# Inverted_Pendulum_Cape.net
KiCad netlist of a schematic drawn in Altium Designer
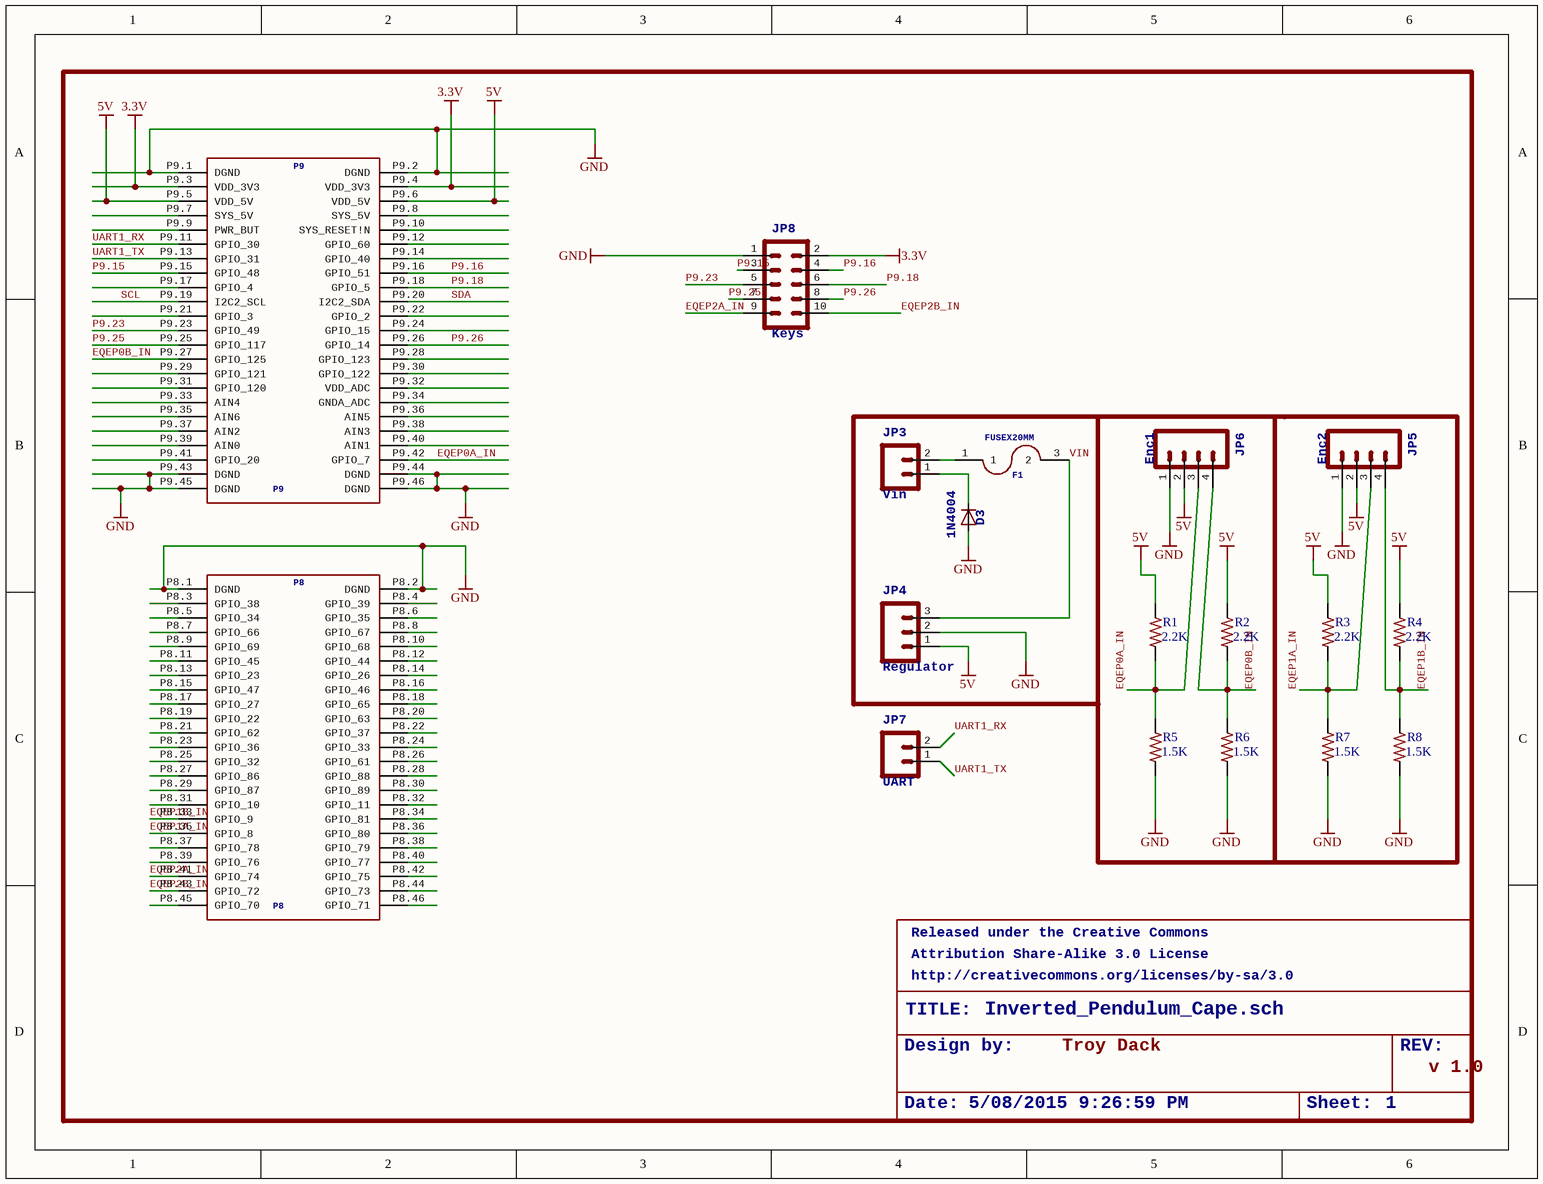
[diagram p0: Inverted_Pendulum_Cape.SchDoc]

(export (version "E")
  (design (tool "Eeschema 10.0.6"))
  (components
    (comp (ref "D3")
      (value "1N4004")
      (footprint "DO41-10")
      (description "<B>DIODE</B><p>\ngeneral purpose rectifier, 1 A")
      (libsource (lib "diode") (part "1N4004"))
    )
    (comp (ref "F1")
      (value "FUSEX20MM")
      (footprint "FUSE_5MM")
      (libsource (lib "SparkFun-Passives") (part "FUSEX20MM"))
    )
    (comp (ref "JP3")
      (value "Vin")
      (footprint "MOLEX-1X2")
      (fields
        (field (name "MF") "MOLEX")
        (field (name "MPN") "22-27-2021")
        (field (name ">VALUE") "Vin")
        (field (name ">NAME") "JP3")
      )
      (libsource (lib "SparkFun-Connectors") (part "M02POLAR"))
    )
    (comp (ref "JP4")
      (value "Regulator")
      (footprint "1X03")
      (fields
        (field (name "MF") "MURATA POWER SOLUTIONS")
        (field (name "MPN") "OKI-78SR-5/1.5-W36-C.")
        (field (name ">VALUE") "Regulator")
        (field (name ">NAME") "JP4")
      )
      (libsource (lib "SparkFun-Connectors") (part "M03PTH"))
    )
    (comp (ref "JP5")
      (value "Enc2")
      (footprint "MOLEX-1X4")
      (fields
        (field (name "MF") "MOLEX")
        (field (name "MPN") "22-27-2041")
        (field (name ">VALUE") "Enc2")
        (field (name ">NAME") "JP5")
      )
      (libsource (lib "SparkFun-Connectors") (part "M04POLAR"))
    )
    (comp (ref "JP6")
      (value "Enc1")
      (footprint "MOLEX-1X4")
      (fields
        (field (name "MF") "MOLEX")
        (field (name "MPN") "22-27-2041")
        (field (name ">VALUE") "Enc1")
        (field (name ">NAME") "JP6")
      )
      (libsource (lib "SparkFun-Connectors") (part "M04POLAR"))
    )
    (comp (ref "JP7")
      (value "UART")
      (footprint "MOLEX-1X2")
      (fields
        (field (name "MF") "MOLEX")
        (field (name "MPN") "22-27-2021")
        (field (name ">VALUE") "UART")
        (field (name ">NAME") "JP7")
      )
      (libsource (lib "SparkFun-Connectors") (part "M02POLAR"))
    )
    (comp (ref "JP8")
      (value "Keys")
      (footprint "2X5_PTH_SILK_.05")
      (libsource (lib "SparkFun-Connectors") (part "M05X20.05_IN_PTH_SILK"))
    )
    (comp (ref "R1")
      (value "2.2K")
      (footprint "1206")
      (fields (field (name "Comment") "RESISTOR1206"))
      (libsource (lib "SparkFun-Passives") (part "RESISTOR1206"))
    )
    (comp (ref "R2")
      (value "2.2K")
      (footprint "1206")
      (fields (field (name "Comment") "RESISTOR1206"))
      (libsource (lib "SparkFun-Passives") (part "RESISTOR1206"))
    )
    (comp (ref "R3")
      (value "2.2K")
      (footprint "1206")
      (fields (field (name "Comment") "RESISTOR1206"))
      (libsource (lib "SparkFun-Passives") (part "RESISTOR1206"))
    )
    (comp (ref "R4")
      (value "2.2K")
      (footprint "1206")
      (fields (field (name "Comment") "RESISTOR1206"))
      (libsource (lib "SparkFun-Passives") (part "RESISTOR1206"))
    )
    (comp (ref "R5")
      (value "1.5K")
      (footprint "1206")
      (fields (field (name "Comment") "RESISTOR1206"))
      (libsource (lib "SparkFun-Passives") (part "RESISTOR1206"))
    )
    (comp (ref "R6")
      (value "1.5K")
      (footprint "1206")
      (fields (field (name "Comment") "RESISTOR1206"))
      (libsource (lib "SparkFun-Passives") (part "RESISTOR1206"))
    )
    (comp (ref "R7")
      (value "1.5K")
      (footprint "1206")
      (fields (field (name "Comment") "RESISTOR1206"))
      (libsource (lib "SparkFun-Passives") (part "RESISTOR1206"))
    )
    (comp (ref "R8")
      (value "1.5K")
      (footprint "1206")
      (fields (field (name "Comment") "RESISTOR1206"))
      (libsource (lib "SparkFun-Passives") (part "RESISTOR1206"))
    )
    (comp (ref "U$1")
      (value "BEAGLE_BONE_BLACK_CAPE")
      (footprint "BEAGLE_BONE_BLACK_CAPE")
      (fields
        (field (name "P8") "P8")
        (field (name "P8_1") "P8")
        (field (name "P9") "P9")
        (field (name "P9_1") "P9")
      )
      (libsource (lib "SparkFun-Boards") (part "BEAGLE_BONE_BLACK_CAPE"))
    )
  )
  (nets
    (net (code "1") (name "/EQEP0A_IN") (class "Default")
      (node (ref "JP6") (pin "3") (pinfunction "3_3") (pintype "passive"))
      (node (ref "R1") (pin "2") (pinfunction "2_2") (pintype "passive"))
      (node (ref "R5") (pin "1") (pinfunction "1_1") (pintype "passive"))
      (node (ref "U$1") (pin "P9.42") (pinfunction "GPIO_7_P9.42") (pintype "passive"))
    )
    (net (code "2") (name "/EQEP0B_IN") (class "Default")
      (node (ref "JP6") (pin "4") (pinfunction "4_4") (pintype "passive"))
      (node (ref "R2") (pin "2") (pinfunction "2_2") (pintype "passive"))
      (node (ref "R6") (pin "1") (pinfunction "1_1") (pintype "passive"))
      (node (ref "U$1") (pin "P9.27") (pinfunction "GPIO_125_P9.27") (pintype "passive"))
    )
    (net (code "3") (name "/EQEP1A_IN") (class "Default")
      (node (ref "JP5") (pin "3") (pinfunction "3_3") (pintype "passive"))
      (node (ref "R3") (pin "2") (pinfunction "2_2") (pintype "passive"))
      (node (ref "R7") (pin "1") (pinfunction "1_1") (pintype "passive"))
      (node (ref "U$1") (pin "P8.35") (pinfunction "GPIO_8_P8.35") (pintype "passive"))
    )
    (net (code "4") (name "/EQEP1B_IN") (class "Default")
      (node (ref "JP5") (pin "4") (pinfunction "4_4") (pintype "passive"))
      (node (ref "R4") (pin "2") (pinfunction "2_2") (pintype "passive"))
      (node (ref "R8") (pin "1") (pinfunction "1_1") (pintype "passive"))
      (node (ref "U$1") (pin "P8.33") (pinfunction "GPIO_9_P8.33") (pintype "passive"))
    )
    (net (code "5") (name "/EQEP2A_IN") (class "Default")
      (node (ref "JP8") (pin "9") (pinfunction "9_9") (pintype "passive"))
      (node (ref "U$1") (pin "P8.41") (pinfunction "GPIO_74_P8.41") (pintype "passive"))
    )
    (net (code "6") (name "/EQEP2B_IN") (class "Default")
      (node (ref "JP8") (pin "10") (pinfunction "10_10") (pintype "passive"))
      (node (ref "U$1") (pin "P8.43") (pinfunction "GPIO_72_P8.43") (pintype "passive"))
    )
    (net (code "7") (name "/P9.15") (class "Default")
      (node (ref "JP8") (pin "3") (pinfunction "3_3") (pintype "passive"))
      (node (ref "U$1") (pin "P9.15") (pinfunction "GPIO_48_P9.15") (pintype "passive"))
    )
    (net (code "8") (name "/P9.16") (class "Default")
      (node (ref "JP8") (pin "4") (pinfunction "4_4") (pintype "passive"))
      (node (ref "U$1") (pin "P9.16") (pinfunction "GPIO_51_P9.16") (pintype "passive"))
    )
    (net (code "9") (name "/P9.18") (class "Default")
      (node (ref "JP8") (pin "6") (pinfunction "6_6") (pintype "passive"))
      (node (ref "U$1") (pin "P9.18") (pinfunction "GPIO_5_P9.18") (pintype "passive"))
    )
    (net (code "10") (name "/P9.23") (class "Default")
      (node (ref "JP8") (pin "5") (pinfunction "5_5") (pintype "passive"))
      (node (ref "U$1") (pin "P9.23") (pinfunction "GPIO_49_P9.23") (pintype "passive"))
    )
    (net (code "11") (name "/P9.25") (class "Default")
      (node (ref "JP8") (pin "7") (pinfunction "7_7") (pintype "passive"))
      (node (ref "U$1") (pin "P9.25") (pinfunction "GPIO_117_P9.25") (pintype "passive"))
    )
    (net (code "12") (name "/P9.26") (class "Default")
      (node (ref "JP8") (pin "8") (pinfunction "8_8") (pintype "passive"))
      (node (ref "U$1") (pin "P9.26") (pinfunction "GPIO_14_P9.26") (pintype "passive"))
    )
    (net (code "13") (name "/SCL") (class "Default")
      (node (ref "U$1") (pin "P9.19") (pinfunction "I2C2_SCL_P9.19") (pintype "passive"))
    )
    (net (code "14") (name "/SDA") (class "Default")
      (node (ref "U$1") (pin "P9.20") (pinfunction "I2C2_SDA_P9.20") (pintype "passive"))
    )
    (net (code "15") (name "/UART1_RX") (class "Default")
      (node (ref "JP7") (pin "2") (pinfunction "2_2") (pintype "passive"))
      (node (ref "U$1") (pin "P9.11") (pinfunction "GPIO_30_P9.11") (pintype "passive"))
    )
    (net (code "16") (name "/UART1_TX") (class "Default")
      (node (ref "JP7") (pin "1") (pinfunction "1_1") (pintype "passive"))
      (node (ref "U$1") (pin "P9.13") (pinfunction "GPIO_31_P9.13") (pintype "passive"))
    )
    (net (code "17") (name "/VIN") (class "Default")
      (node (ref "F1") (pin "3") (pinfunction "2_3") (pintype "passive"))
      (node (ref "JP4") (pin "3") (pinfunction "3_3") (pintype "passive"))
    )
    (net (code "18") (name "3.3V") (class "Default")
      (node (ref "JP8") (pin "2") (pinfunction "2_2") (pintype "passive"))
      (node (ref "U$1") (pin "P9.3") (pinfunction "VDD_3V3_P9.3") (pintype "passive"))
      (node (ref "U$1") (pin "P9.4") (pinfunction "VDD_3V3_P9.4") (pintype "passive"))
    )
    (net (code "19") (name "5V") (class "Default")
      (node (ref "JP4") (pin "1") (pinfunction "1_1") (pintype "passive"))
      (node (ref "JP5") (pin "2") (pinfunction "2_2") (pintype "passive"))
      (node (ref "JP6") (pin "2") (pinfunction "2_2") (pintype "passive"))
      (node (ref "R1") (pin "1") (pinfunction "1_1") (pintype "passive"))
      (node (ref "R2") (pin "1") (pinfunction "1_1") (pintype "passive"))
      (node (ref "R3") (pin "1") (pinfunction "1_1") (pintype "passive"))
      (node (ref "R4") (pin "1") (pinfunction "1_1") (pintype "passive"))
      (node (ref "U$1") (pin "P9.5") (pinfunction "VDD_5V_P9.5") (pintype "passive"))
      (node (ref "U$1") (pin "P9.6") (pinfunction "VDD_5V_P9.6") (pintype "passive"))
    )
    (net (code "20") (name "GND") (class "Default")
      (node (ref "D3") (pin "A") (pinfunction "A_A") (pintype "passive"))
      (node (ref "JP4") (pin "2") (pinfunction "2_2") (pintype "passive"))
      (node (ref "JP5") (pin "1") (pinfunction "1_1") (pintype "passive"))
      (node (ref "JP6") (pin "1") (pinfunction "1_1") (pintype "passive"))
      (node (ref "JP8") (pin "1") (pinfunction "1_1") (pintype "passive"))
      (node (ref "R5") (pin "2") (pinfunction "2_2") (pintype "passive"))
      (node (ref "R6") (pin "2") (pinfunction "2_2") (pintype "passive"))
      (node (ref "R7") (pin "2") (pinfunction "2_2") (pintype "passive"))
      (node (ref "R8") (pin "2") (pinfunction "2_2") (pintype "passive"))
      (node (ref "U$1") (pin "P8.1") (pinfunction "DGND_P8.1") (pintype "passive"))
      (node (ref "U$1") (pin "P8.2") (pinfunction "DGND_P8.2") (pintype "passive"))
      (node (ref "U$1") (pin "P9.1") (pinfunction "DGND_P9.1") (pintype "passive"))
      (node (ref "U$1") (pin "P9.2") (pinfunction "DGND_P9.2") (pintype "passive"))
      (node (ref "U$1") (pin "P9.43") (pinfunction "DGND_P9.43") (pintype "passive"))
      (node (ref "U$1") (pin "P9.44") (pinfunction "DGND_P9.44") (pintype "passive"))
      (node (ref "U$1") (pin "P9.45") (pinfunction "DGND_P9.45") (pintype "passive"))
      (node (ref "U$1") (pin "P9.46") (pinfunction "DGND_P9.46") (pintype "passive"))
    )
    (net (code "21") (name "Net-(D3-PadC)") (class "Default")
      (node (ref "D3") (pin "C") (pinfunction "C_C") (pintype "passive"))
      (node (ref "JP3") (pin "1") (pinfunction "1_1") (pintype "passive"))
    )
    (net (code "22") (name "Net-(F1-Pad1)") (class "Default")
      (node (ref "F1") (pin "1") (pinfunction "1_1") (pintype "passive"))
      (node (ref "JP3") (pin "2") (pinfunction "2_2") (pintype "passive"))
    )
    (net (code "23") (name "unconnected-(U$1A-GPIO_10-PadP8.31)") (class "Default")
      (node (ref "U$1") (pin "P8.31") (pinfunction "GPIO_10_P8.31") (pintype "passive"))
    )
    (net (code "24") (name "unconnected-(U$1A-GPIO_11-PadP8.32)") (class "Default")
      (node (ref "U$1") (pin "P8.32") (pinfunction "GPIO_11_P8.32") (pintype "passive"))
    )
    (net (code "25") (name "unconnected-(U$1A-GPIO_22-PadP8.19)") (class "Default")
      (node (ref "U$1") (pin "P8.19") (pinfunction "GPIO_22_P8.19") (pintype "passive"))
    )
    (net (code "26") (name "unconnected-(U$1A-GPIO_23-PadP8.13)") (class "Default")
      (node (ref "U$1") (pin "P8.13") (pinfunction "GPIO_23_P8.13") (pintype "passive"))
    )
    (net (code "27") (name "unconnected-(U$1A-GPIO_26-PadP8.14)") (class "Default")
      (node (ref "U$1") (pin "P8.14") (pinfunction "GPIO_26_P8.14") (pintype "passive"))
    )
    (net (code "28") (name "unconnected-(U$1A-GPIO_27-PadP8.17)") (class "Default")
      (node (ref "U$1") (pin "P8.17") (pinfunction "GPIO_27_P8.17") (pintype "passive"))
    )
    (net (code "29") (name "unconnected-(U$1A-GPIO_32-PadP8.25)") (class "Default")
      (node (ref "U$1") (pin "P8.25") (pinfunction "GPIO_32_P8.25") (pintype "passive"))
    )
    (net (code "30") (name "unconnected-(U$1A-GPIO_33-PadP8.24)") (class "Default")
      (node (ref "U$1") (pin "P8.24") (pinfunction "GPIO_33_P8.24") (pintype "passive"))
    )
    (net (code "31") (name "unconnected-(U$1A-GPIO_34-PadP8.5)") (class "Default")
      (node (ref "U$1") (pin "P8.5") (pinfunction "GPIO_34_P8.5") (pintype "passive"))
    )
    (net (code "32") (name "unconnected-(U$1A-GPIO_35-PadP8.6)") (class "Default")
      (node (ref "U$1") (pin "P8.6") (pinfunction "GPIO_35_P8.6") (pintype "passive"))
    )
    (net (code "33") (name "unconnected-(U$1A-GPIO_36-PadP8.23)") (class "Default")
      (node (ref "U$1") (pin "P8.23") (pinfunction "GPIO_36_P8.23") (pintype "passive"))
    )
    (net (code "34") (name "unconnected-(U$1A-GPIO_37-PadP8.22)") (class "Default")
      (node (ref "U$1") (pin "P8.22") (pinfunction "GPIO_37_P8.22") (pintype "passive"))
    )
    (net (code "35") (name "unconnected-(U$1A-GPIO_38-PadP8.3)") (class "Default")
      (node (ref "U$1") (pin "P8.3") (pinfunction "GPIO_38_P8.3") (pintype "passive"))
    )
    (net (code "36") (name "unconnected-(U$1A-GPIO_39-PadP8.4)") (class "Default")
      (node (ref "U$1") (pin "P8.4") (pinfunction "GPIO_39_P8.4") (pintype "passive"))
    )
    (net (code "37") (name "unconnected-(U$1A-GPIO_44-PadP8.12)") (class "Default")
      (node (ref "U$1") (pin "P8.12") (pinfunction "GPIO_44_P8.12") (pintype "passive"))
    )
    (net (code "38") (name "unconnected-(U$1A-GPIO_45-PadP8.11)") (class "Default")
      (node (ref "U$1") (pin "P8.11") (pinfunction "GPIO_45_P8.11") (pintype "passive"))
    )
    (net (code "39") (name "unconnected-(U$1A-GPIO_46-PadP8.16)") (class "Default")
      (node (ref "U$1") (pin "P8.16") (pinfunction "GPIO_46_P8.16") (pintype "passive"))
    )
    (net (code "40") (name "unconnected-(U$1A-GPIO_47-PadP8.15)") (class "Default")
      (node (ref "U$1") (pin "P8.15") (pinfunction "GPIO_47_P8.15") (pintype "passive"))
    )
    (net (code "41") (name "unconnected-(U$1A-GPIO_61-PadP8.26)") (class "Default")
      (node (ref "U$1") (pin "P8.26") (pinfunction "GPIO_61_P8.26") (pintype "passive"))
    )
    (net (code "42") (name "unconnected-(U$1A-GPIO_62-PadP8.21)") (class "Default")
      (node (ref "U$1") (pin "P8.21") (pinfunction "GPIO_62_P8.21") (pintype "passive"))
    )
    (net (code "43") (name "unconnected-(U$1A-GPIO_63-PadP8.20)") (class "Default")
      (node (ref "U$1") (pin "P8.20") (pinfunction "GPIO_63_P8.20") (pintype "passive"))
    )
    (net (code "44") (name "unconnected-(U$1A-GPIO_65-PadP8.18)") (class "Default")
      (node (ref "U$1") (pin "P8.18") (pinfunction "GPIO_65_P8.18") (pintype "passive"))
    )
    (net (code "45") (name "unconnected-(U$1A-GPIO_66-PadP8.7)") (class "Default")
      (node (ref "U$1") (pin "P8.7") (pinfunction "GPIO_66_P8.7") (pintype "passive"))
    )
    (net (code "46") (name "unconnected-(U$1A-GPIO_67-PadP8.8)") (class "Default")
      (node (ref "U$1") (pin "P8.8") (pinfunction "GPIO_67_P8.8") (pintype "passive"))
    )
    (net (code "47") (name "unconnected-(U$1A-GPIO_68-PadP8.10)") (class "Default")
      (node (ref "U$1") (pin "P8.10") (pinfunction "GPIO_68_P8.10") (pintype "passive"))
    )
    (net (code "48") (name "unconnected-(U$1A-GPIO_69-PadP8.9)") (class "Default")
      (node (ref "U$1") (pin "P8.9") (pinfunction "GPIO_69_P8.9") (pintype "passive"))
    )
    (net (code "49") (name "unconnected-(U$1A-GPIO_70-PadP8.45)") (class "Default")
      (node (ref "U$1") (pin "P8.45") (pinfunction "GPIO_70_P8.45") (pintype "passive"))
    )
    (net (code "50") (name "unconnected-(U$1A-GPIO_71-PadP8.46)") (class "Default")
      (node (ref "U$1") (pin "P8.46") (pinfunction "GPIO_71_P8.46") (pintype "passive"))
    )
    (net (code "51") (name "unconnected-(U$1A-GPIO_73-PadP8.44)") (class "Default")
      (node (ref "U$1") (pin "P8.44") (pinfunction "GPIO_73_P8.44") (pintype "passive"))
    )
    (net (code "52") (name "unconnected-(U$1A-GPIO_75-PadP8.42)") (class "Default")
      (node (ref "U$1") (pin "P8.42") (pinfunction "GPIO_75_P8.42") (pintype "passive"))
    )
    (net (code "53") (name "unconnected-(U$1A-GPIO_76-PadP8.39)") (class "Default")
      (node (ref "U$1") (pin "P8.39") (pinfunction "GPIO_76_P8.39") (pintype "passive"))
    )
    (net (code "54") (name "unconnected-(U$1A-GPIO_77-PadP8.40)") (class "Default")
      (node (ref "U$1") (pin "P8.40") (pinfunction "GPIO_77_P8.40") (pintype "passive"))
    )
    (net (code "55") (name "unconnected-(U$1A-GPIO_78-PadP8.37)") (class "Default")
      (node (ref "U$1") (pin "P8.37") (pinfunction "GPIO_78_P8.37") (pintype "passive"))
    )
    (net (code "56") (name "unconnected-(U$1A-GPIO_79-PadP8.38)") (class "Default")
      (node (ref "U$1") (pin "P8.38") (pinfunction "GPIO_79_P8.38") (pintype "passive"))
    )
    (net (code "57") (name "unconnected-(U$1A-GPIO_80-PadP8.36)") (class "Default")
      (node (ref "U$1") (pin "P8.36") (pinfunction "GPIO_80_P8.36") (pintype "passive"))
    )
    (net (code "58") (name "unconnected-(U$1A-GPIO_81-PadP8.34)") (class "Default")
      (node (ref "U$1") (pin "P8.34") (pinfunction "GPIO_81_P8.34") (pintype "passive"))
    )
    (net (code "59") (name "unconnected-(U$1A-GPIO_86-PadP8.27)") (class "Default")
      (node (ref "U$1") (pin "P8.27") (pinfunction "GPIO_86_P8.27") (pintype "passive"))
    )
    (net (code "60") (name "unconnected-(U$1A-GPIO_87-PadP8.29)") (class "Default")
      (node (ref "U$1") (pin "P8.29") (pinfunction "GPIO_87_P8.29") (pintype "passive"))
    )
    (net (code "61") (name "unconnected-(U$1A-GPIO_88-PadP8.28)") (class "Default")
      (node (ref "U$1") (pin "P8.28") (pinfunction "GPIO_88_P8.28") (pintype "passive"))
    )
    (net (code "62") (name "unconnected-(U$1A-GPIO_89-PadP8.30)") (class "Default")
      (node (ref "U$1") (pin "P8.30") (pinfunction "GPIO_89_P8.30") (pintype "passive"))
    )
    (net (code "63") (name "unconnected-(U$1B-AIN0-PadP9.39)") (class "Default")
      (node (ref "U$1") (pin "P9.39") (pinfunction "AIN0_P9.39") (pintype "passive"))
    )
    (net (code "64") (name "unconnected-(U$1B-AIN1-PadP9.40)") (class "Default")
      (node (ref "U$1") (pin "P9.40") (pinfunction "AIN1_P9.40") (pintype "passive"))
    )
    (net (code "65") (name "unconnected-(U$1B-AIN2-PadP9.37)") (class "Default")
      (node (ref "U$1") (pin "P9.37") (pinfunction "AIN2_P9.37") (pintype "passive"))
    )
    (net (code "66") (name "unconnected-(U$1B-AIN3-PadP9.38)") (class "Default")
      (node (ref "U$1") (pin "P9.38") (pinfunction "AIN3_P9.38") (pintype "passive"))
    )
    (net (code "67") (name "unconnected-(U$1B-AIN4-PadP9.33)") (class "Default")
      (node (ref "U$1") (pin "P9.33") (pinfunction "AIN4_P9.33") (pintype "passive"))
    )
    (net (code "68") (name "unconnected-(U$1B-AIN5-PadP9.36)") (class "Default")
      (node (ref "U$1") (pin "P9.36") (pinfunction "AIN5_P9.36") (pintype "passive"))
    )
    (net (code "69") (name "unconnected-(U$1B-AIN6-PadP9.35)") (class "Default")
      (node (ref "U$1") (pin "P9.35") (pinfunction "AIN6_P9.35") (pintype "passive"))
    )
    (net (code "70") (name "unconnected-(U$1B-GNDA_ADC-PadP9.34)") (class "Default")
      (node (ref "U$1") (pin "P9.34") (pinfunction "GNDA_ADC_P9.34") (pintype "passive"))
    )
    (net (code "71") (name "unconnected-(U$1B-GPIO_2-PadP9.22)") (class "Default")
      (node (ref "U$1") (pin "P9.22") (pinfunction "GPIO_2_P9.22") (pintype "passive"))
    )
    (net (code "72") (name "unconnected-(U$1B-GPIO_3-PadP9.21)") (class "Default")
      (node (ref "U$1") (pin "P9.21") (pinfunction "GPIO_3_P9.21") (pintype "passive"))
    )
    (net (code "73") (name "unconnected-(U$1B-GPIO_4-PadP9.17)") (class "Default")
      (node (ref "U$1") (pin "P9.17") (pinfunction "GPIO_4_P9.17") (pintype "passive"))
    )
    (net (code "74") (name "unconnected-(U$1B-GPIO_15-PadP9.24)") (class "Default")
      (node (ref "U$1") (pin "P9.24") (pinfunction "GPIO_15_P9.24") (pintype "passive"))
    )
    (net (code "75") (name "unconnected-(U$1B-GPIO_20-PadP9.41)") (class "Default")
      (node (ref "U$1") (pin "P9.41") (pinfunction "GPIO_20_P9.41") (pintype "passive"))
    )
    (net (code "76") (name "unconnected-(U$1B-GPIO_40-PadP9.14)") (class "Default")
      (node (ref "U$1") (pin "P9.14") (pinfunction "GPIO_40_P9.14") (pintype "passive"))
    )
    (net (code "77") (name "unconnected-(U$1B-GPIO_60-PadP9.12)") (class "Default")
      (node (ref "U$1") (pin "P9.12") (pinfunction "GPIO_60_P9.12") (pintype "passive"))
    )
    (net (code "78") (name "unconnected-(U$1B-GPIO_120-PadP9.31)") (class "Default")
      (node (ref "U$1") (pin "P9.31") (pinfunction "GPIO_120_P9.31") (pintype "passive"))
    )
    (net (code "79") (name "unconnected-(U$1B-GPIO_121-PadP9.29)") (class "Default")
      (node (ref "U$1") (pin "P9.29") (pinfunction "GPIO_121_P9.29") (pintype "passive"))
    )
    (net (code "80") (name "unconnected-(U$1B-GPIO_122-PadP9.30)") (class "Default")
      (node (ref "U$1") (pin "P9.30") (pinfunction "GPIO_122_P9.30") (pintype "passive"))
    )
    (net (code "81") (name "unconnected-(U$1B-GPIO_123-PadP9.28)") (class "Default")
      (node (ref "U$1") (pin "P9.28") (pinfunction "GPIO_123_P9.28") (pintype "passive"))
    )
    (net (code "82") (name "unconnected-(U$1B-PWR_BUT-PadP9.9)") (class "Default")
      (node (ref "U$1") (pin "P9.9") (pinfunction "PWR_BUT_P9.9") (pintype "passive"))
    )
    (net (code "83") (name "unconnected-(U$1B-SYS_5V-PadP9.7)") (class "Default")
      (node (ref "U$1") (pin "P9.7") (pinfunction "SYS_5V_P9.7") (pintype "passive"))
    )
    (net (code "84") (name "unconnected-(U$1B-SYS_5V-PadP9.8)") (class "Default")
      (node (ref "U$1") (pin "P9.8") (pinfunction "SYS_5V_P9.8") (pintype "passive"))
    )
    (net (code "85") (name "unconnected-(U$1B-SYS_RESET!N-PadP9.10)") (class "Default")
      (node (ref "U$1") (pin "P9.10") (pinfunction "SYS_RESET!N_P9.10") (pintype "passive"))
    )
    (net (code "86") (name "unconnected-(U$1B-VDD_ADC-PadP9.32)") (class "Default")
      (node (ref "U$1") (pin "P9.32") (pinfunction "VDD_ADC_P9.32") (pintype "passive"))
    )
  )
)
